# lora_mini_uno.net
KiCad netlist of a schematic drawn in EAGLE
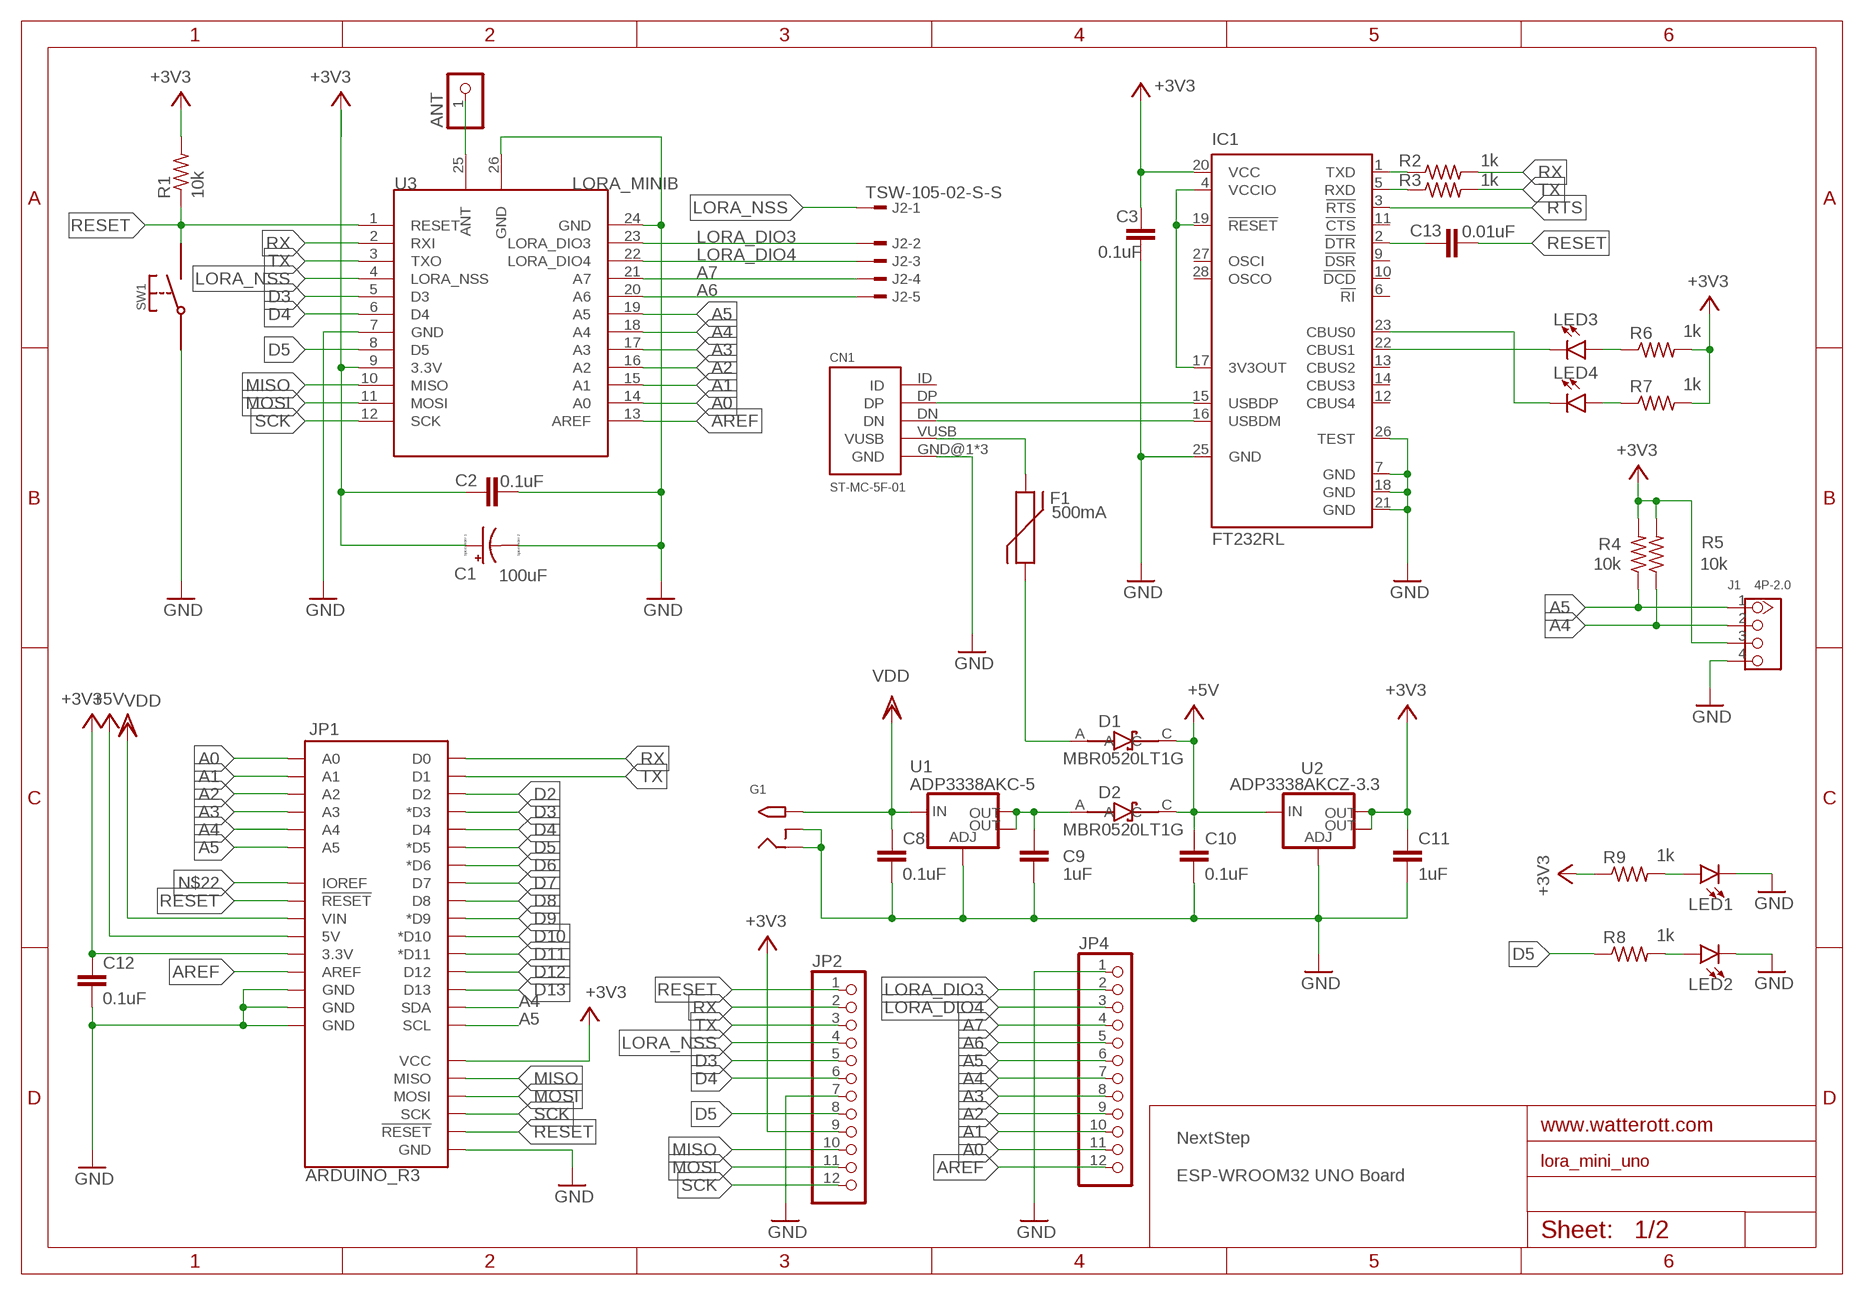
[diagram p0: schematic, sheet 1]
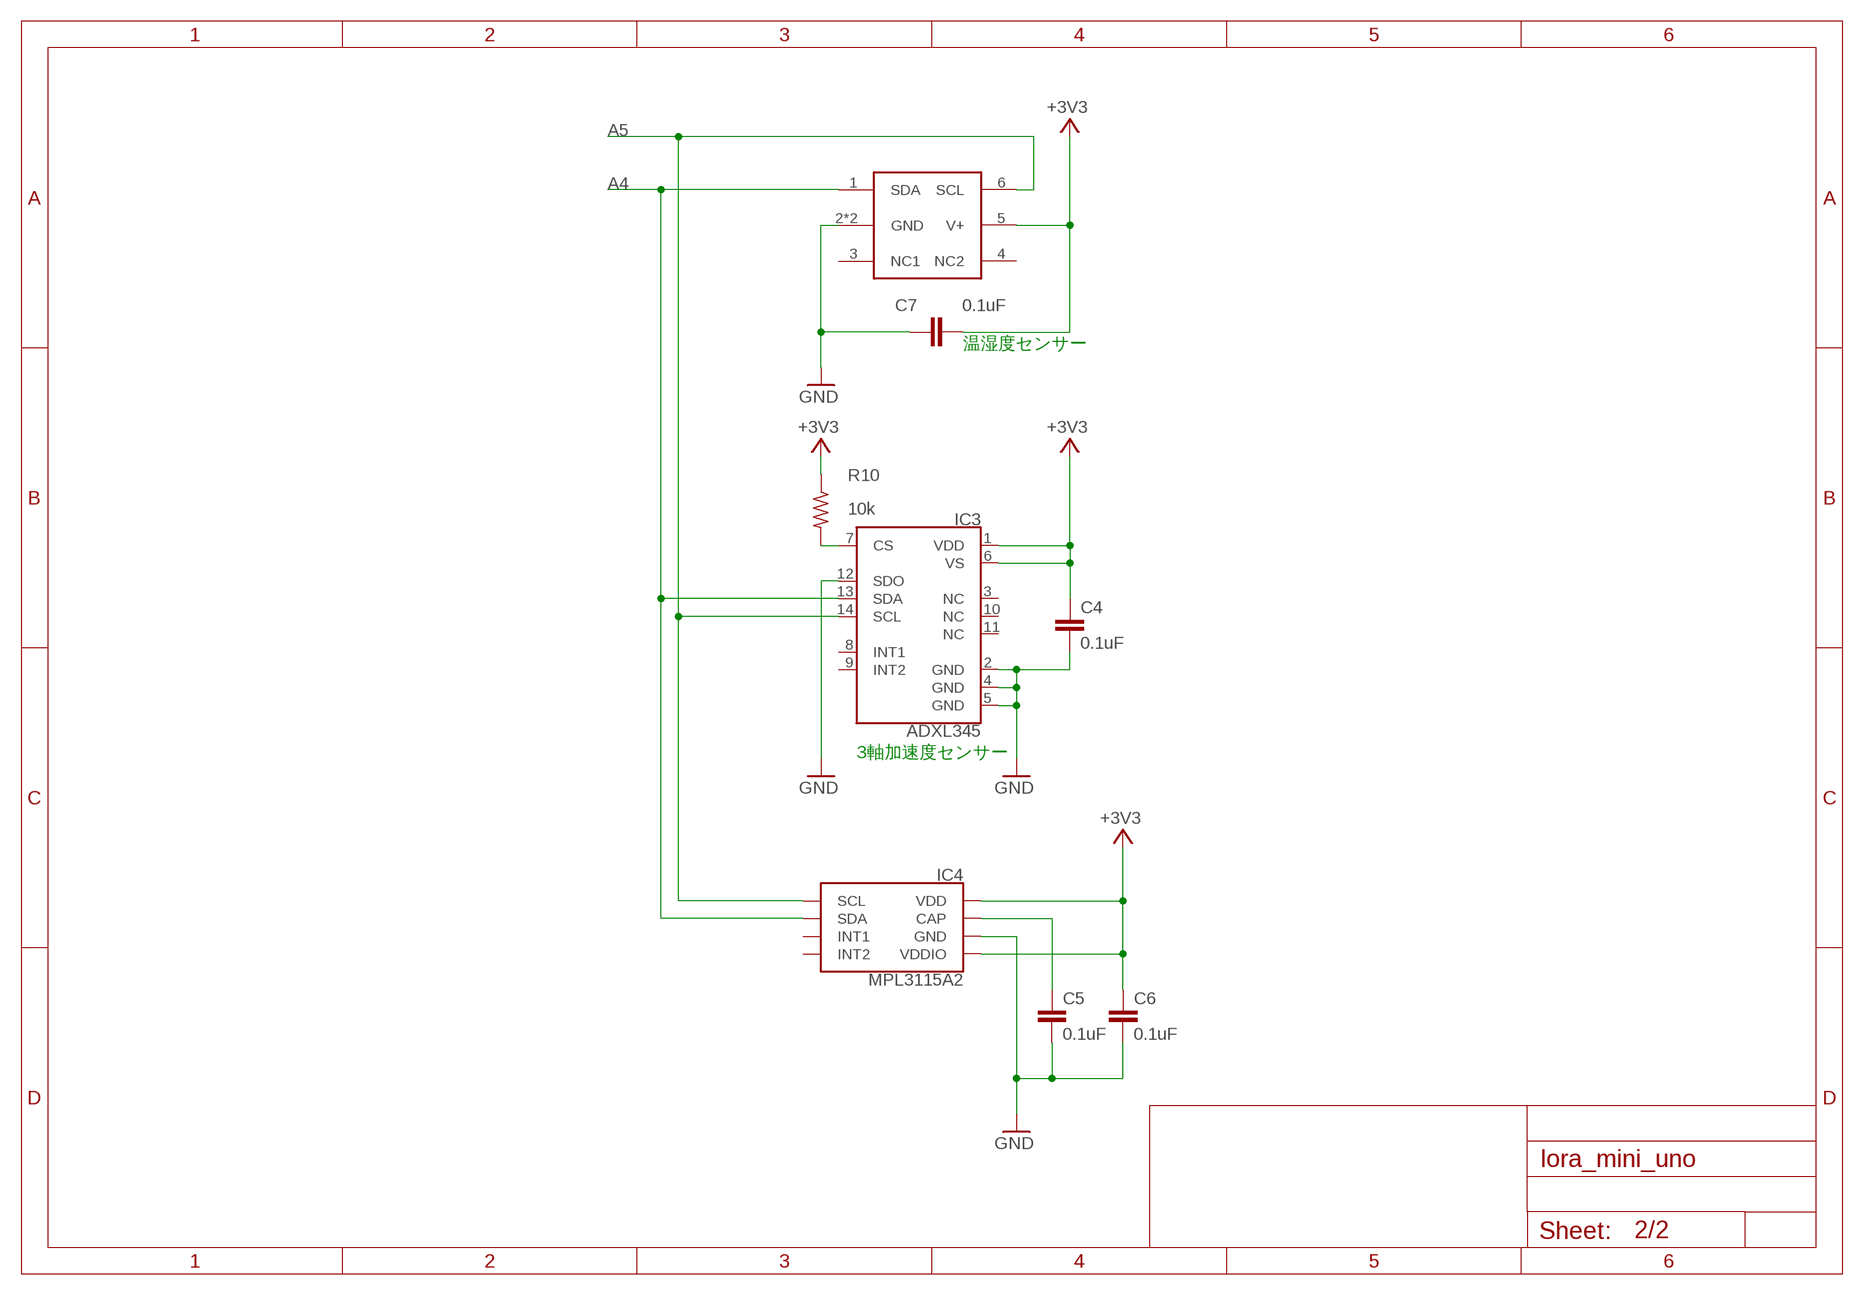
[diagram p1: schematic, sheet 2]

(export (version "E")
  (design (tool "Eeschema 10.0.6"))
  (components
    (comp (ref "ANT")
      (value "PINHD-1X1")
      (footprint "eagle-import:1X01")
      (libsource (lib "eagle-import") (part "PINHD-1X1"))
    )
    (comp (ref "C1")
      (value "100uF")
      (footprint "eagle-import:153CLV-0505")
      (libsource (lib "eagle-import") (part "CPOL-US153CLV-0505"))
    )
    (comp (ref "C2")
      (value "0.1uF")
      (footprint "eagle-import:C0603K")
      (libsource (lib "eagle-import") (part "C-EUC0603K"))
    )
    (comp (ref "C3")
      (value "0.1uF")
      (footprint "eagle-import:C0603K")
      (libsource (lib "eagle-import") (part "C-EUC0603K"))
    )
    (comp (ref "C8")
      (value "0.1uF")
      (footprint "eagle-import:C0603K")
      (libsource (lib "eagle-import") (part "C-EUC0603K"))
    )
    (comp (ref "C9")
      (value "1uF")
      (footprint "eagle-import:C0603K")
      (libsource (lib "eagle-import") (part "C-EUC0603K"))
    )
    (comp (ref "C10")
      (value "0.1uF")
      (footprint "eagle-import:C0603K")
      (libsource (lib "eagle-import") (part "C-EUC0603K"))
    )
    (comp (ref "C11")
      (value "1uF")
      (footprint "eagle-import:C0603K")
      (libsource (lib "eagle-import") (part "C-EUC0603K"))
    )
    (comp (ref "C12")
      (value "0.1uF")
      (footprint "eagle-import:C0603K")
      (libsource (lib "eagle-import") (part "C-EUC0603K"))
    )
    (comp (ref "C13")
      (value "0.01uF")
      (footprint "eagle-import:C0603K")
      (libsource (lib "eagle-import") (part "C-EUC0603K"))
    )
    (comp (ref "CN1")
      (value "ST-MC-5F-01")
      (footprint "eagle-import:ST-MC-5F-01")
      (libsource (lib "eagle-import") (part "ST-MC-5F-01"))
    )
    (comp (ref "D1")
      (value "MBR0520LT1G")
      (footprint "eagle-import:SOD3716X135N")
      (fields (field (name "MF") "ON Semiconductor"))
      (libsource (lib "eagle-import") (part "MBR0520LT1G"))
    )
    (comp (ref "D2")
      (value "MBR0520LT1G")
      (footprint "eagle-import:SOD3716X135N")
      (fields (field (name "MF") "ON Semiconductor"))
      (libsource (lib "eagle-import") (part "MBR0520LT1G"))
    )
    (comp (ref "F1")
      (value "500mA")
      (footprint "eagle-import:R1206")
      (libsource (lib "eagle-import") (part "FUSE1206"))
    )
    (comp (ref "G1")
      (value "2.1MMJACKTHM")
      (footprint "eagle-import:PJ-102A")
      (libsource (lib "eagle-import") (part "2.1MMJACKTHM"))
    )
    (comp (ref "IC1")
      (value "FT232RL")
      (footprint "eagle-import:SSOP28")
      (libsource (lib "eagle-import") (part "FT232RL"))
    )
    (comp (ref "J1")
      (value "4P-2.0")
      (footprint "eagle-import:HW4-2.0")
      (libsource (lib "eagle-import") (part "GROVE-CONNECTOR-DIP(4P-2.0)"))
    )
    (comp (ref "J2")
      (value "TSW-105-02-S-S")
      (footprint "eagle-import:TSW-105-02-S-S")
      (libsource (lib "eagle-import") (part "TSW-105-02-S-S"))
    )
    (comp (ref "JP1")
      (value "ARDUINO_R3")
      (footprint "eagle-import:ARDUINO_R3")
      (libsource (lib "eagle-import") (part "ARDUINO_R3"))
    )
    (comp (ref "JP2")
      (value "PINHD-1X12-CB")
      (footprint "eagle-import:1X12-CB")
      (libsource (lib "eagle-import") (part "PINHD-1X12-CB"))
    )
    (comp (ref "JP4")
      (value "PINHD-1X12-CB")
      (footprint "eagle-import:1X12-CB")
      (libsource (lib "eagle-import") (part "PINHD-1X12-CB"))
    )
    (comp (ref "LED1")
      (value "LED0603")
      (footprint "eagle-import:LED-0603")
      (libsource (lib "eagle-import") (part "LED0603"))
    )
    (comp (ref "LED2")
      (value "LED0603")
      (footprint "eagle-import:LED-0603")
      (libsource (lib "eagle-import") (part "LED0603"))
    )
    (comp (ref "LED3")
      (value "LED0603")
      (footprint "eagle-import:LED-0603")
      (libsource (lib "eagle-import") (part "LED0603"))
    )
    (comp (ref "LED4")
      (value "LED0603")
      (footprint "eagle-import:LED-0603")
      (libsource (lib "eagle-import") (part "LED0603"))
    )
    (comp (ref "R1")
      (value "10k")
      (footprint "eagle-import:R0603")
      (libsource (lib "eagle-import") (part "R-US_R0603"))
    )
    (comp (ref "R2")
      (value "1k")
      (footprint "eagle-import:R0603")
      (libsource (lib "eagle-import") (part "R-US_R0603"))
    )
    (comp (ref "R3")
      (value "1k")
      (footprint "eagle-import:R0603")
      (libsource (lib "eagle-import") (part "R-US_R0603"))
    )
    (comp (ref "R4")
      (value "10k")
      (footprint "eagle-import:R0603")
      (libsource (lib "eagle-import") (part "R-US_R0603"))
    )
    (comp (ref "R5")
      (value "10k")
      (footprint "eagle-import:R0603")
      (libsource (lib "eagle-import") (part "R-US_R0603"))
    )
    (comp (ref "R6")
      (value "1k")
      (footprint "eagle-import:R0603")
      (libsource (lib "eagle-import") (part "R-US_R0603"))
    )
    (comp (ref "R7")
      (value "1k")
      (footprint "eagle-import:R0603")
      (libsource (lib "eagle-import") (part "R-US_R0603"))
    )
    (comp (ref "R8")
      (value "1k")
      (footprint "eagle-import:R0603")
      (libsource (lib "eagle-import") (part "R-US_R0603"))
    )
    (comp (ref "R9")
      (value "1k")
      (footprint "eagle-import:R0603")
      (libsource (lib "eagle-import") (part "R-US_R0603"))
    )
    (comp (ref "SW1")
      (value "RESET")
      (footprint "eagle-import:SWITCH_3X6X5MM")
      (libsource (lib "eagle-import") (part "SWITCH"))
    )
    (comp (ref "U1")
      (value "ADP3338AKC-5")
      (footprint "eagle-import:SOT223")
      (libsource (lib "eagle-import") (part "V_REG_LM1117SOT223"))
    )
    (comp (ref "U2")
      (value "ADP3338AKCZ-3.3")
      (footprint "eagle-import:SOT223")
      (libsource (lib "eagle-import") (part "V_REG_LM1117SOT223"))
    )
    (comp (ref "U3")
      (value "LORA_MINIB")
      (footprint "eagle-import:LORA_MINI_PCB")
      (libsource (lib "eagle-import") (part "LORA_MINIB"))
    )
    (comp (ref "C4")
      (value "0.1uF")
      (footprint "eagle-import:C0603K")
      (libsource (lib "eagle-import") (part "C-EUC0603K"))
    )
    (comp (ref "C5")
      (value "0.1uF")
      (footprint "eagle-import:C0603K")
      (libsource (lib "eagle-import") (part "C-EUC0603K"))
    )
    (comp (ref "C6")
      (value "0.1uF")
      (footprint "eagle-import:C0603K")
      (libsource (lib "eagle-import") (part "C-EUC0603K"))
    )
    (comp (ref "C7")
      (value "0.1uF")
      (footprint "eagle-import:C0603K")
      (libsource (lib "eagle-import") (part "C-EUC0603K"))
    )
    (comp (ref "IC2")
      (value "SHT21")
      (footprint "eagle-import:SHT21")
      (libsource (lib "eagle-import") (part "SHT21"))
    )
    (comp (ref "IC3")
      (value "ADXL345")
      (footprint "eagle-import:LGA-14")
      (libsource (lib "eagle-import") (part "ADXL345"))
    )
    (comp (ref "IC4")
      (value "MPL3115A2")
      (footprint "eagle-import:LGA-8-5X3")
      (libsource (lib "eagle-import") (part "MPL3115A2"))
    )
    (comp (ref "R10")
      (value "10k")
      (footprint "eagle-import:R0603")
      (libsource (lib "eagle-import") (part "R-US_R0603"))
    )
  )
  (nets
    (net (code "1") (name "+3V3") (class "Default")
      (node (ref "C1") (pin "+") (pinfunction "+_+") (pintype "passive"))
      (node (ref "C11") (pin "1") (pinfunction "1_1") (pintype "passive"))
      (node (ref "C12") (pin "1") (pinfunction "1_1") (pintype "passive"))
      (node (ref "C2") (pin "1") (pinfunction "1_1") (pintype "passive"))
      (node (ref "C3") (pin "1") (pinfunction "1_1") (pintype "passive"))
      (node (ref "C4") (pin "1") (pinfunction "1_1") (pintype "passive"))
      (node (ref "C6") (pin "1") (pinfunction "1_1") (pintype "passive"))
      (node (ref "C7") (pin "2") (pinfunction "2_2") (pintype "passive"))
      (node (ref "IC1") (pin "20") (pinfunction "VCC_20") (pintype "power_in"))
      (node (ref "IC2") (pin "5") (pinfunction "V+_5") (pintype "bidirectional"))
      (node (ref "IC3") (pin "1") (pinfunction "VDD_1") (pintype "bidirectional"))
      (node (ref "IC3") (pin "6") (pinfunction "VS_6") (pintype "bidirectional"))
      (node (ref "IC4") (pin "1") (pinfunction "VDD_1") (pintype "power_in"))
      (node (ref "IC4") (pin "4") (pinfunction "VDDIO_4") (pintype "power_in"))
      (node (ref "J1") (pin "3") (pinfunction "3_3") (pintype "bidirectional"))
      (node (ref "JP1") (pin "3.3V") (pinfunction "3.3V_3.3V") (pintype "bidirectional"))
      (node (ref "JP1") (pin "VCC") (pinfunction "VCC_VCC") (pintype "bidirectional"))
      (node (ref "JP2") (pin "9") (pinfunction "9_9") (pintype "passive"))
      (node (ref "R1") (pin "2") (pinfunction "2_2") (pintype "passive"))
      (node (ref "R10") (pin "1") (pinfunction "1_1") (pintype "passive"))
      (node (ref "R4") (pin "2") (pinfunction "2_2") (pintype "passive"))
      (node (ref "R5") (pin "2") (pinfunction "2_2") (pintype "passive"))
      (node (ref "R6") (pin "2") (pinfunction "2_2") (pintype "passive"))
      (node (ref "R7") (pin "2") (pinfunction "2_2") (pintype "passive"))
      (node (ref "R9") (pin "1") (pinfunction "1_1") (pintype "passive"))
      (node (ref "U2") (pin "2") (pinfunction "OUT_2") (pintype "output"))
      (node (ref "U2") (pin "4") (pinfunction "OUT_4") (pintype "output"))
      (node (ref "U3") (pin "9") (pinfunction "3.3V_9") (pintype "bidirectional"))
    )
    (net (code "2") (name "+5V") (class "Default")
      (node (ref "C10") (pin "1") (pinfunction "1_1") (pintype "passive"))
      (node (ref "D1") (pin "C") (pinfunction "C_C") (pintype "passive"))
      (node (ref "D2") (pin "C") (pinfunction "C_C") (pintype "passive"))
      (node (ref "JP1") (pin "5V") (pinfunction "5V_5V") (pintype "bidirectional"))
      (node (ref "U2") (pin "3") (pinfunction "IN_3") (pintype "input"))
    )
    (net (code "3") (name "A0") (class "Default")
      (node (ref "JP1") (pin "A0") (pinfunction "A0_A0") (pintype "bidirectional"))
      (node (ref "JP4") (pin "11") (pinfunction "11_11") (pintype "passive"))
      (node (ref "U3") (pin "14") (pinfunction "A0_14") (pintype "bidirectional"))
    )
    (net (code "4") (name "A1") (class "Default")
      (node (ref "JP1") (pin "A1") (pinfunction "A1_A1") (pintype "bidirectional"))
      (node (ref "JP4") (pin "10") (pinfunction "10_10") (pintype "passive"))
      (node (ref "U3") (pin "15") (pinfunction "A1_15") (pintype "bidirectional"))
    )
    (net (code "5") (name "A2") (class "Default")
      (node (ref "JP1") (pin "A2") (pinfunction "A2_A2") (pintype "bidirectional"))
      (node (ref "JP4") (pin "9") (pinfunction "9_9") (pintype "passive"))
      (node (ref "U3") (pin "16") (pinfunction "A2_16") (pintype "bidirectional"))
    )
    (net (code "6") (name "A3") (class "Default")
      (node (ref "JP1") (pin "A3") (pinfunction "A3_A3") (pintype "bidirectional"))
      (node (ref "JP4") (pin "8") (pinfunction "8_8") (pintype "passive"))
      (node (ref "U3") (pin "17") (pinfunction "A3_17") (pintype "bidirectional"))
    )
    (net (code "7") (name "A4") (class "Default")
      (node (ref "IC2") (pin "1") (pinfunction "SDA_1") (pintype "bidirectional"))
      (node (ref "IC3") (pin "13") (pinfunction "SDA_13") (pintype "bidirectional"))
      (node (ref "IC4") (pin "7") (pinfunction "SDA_7") (pintype "bidirectional"))
      (node (ref "J1") (pin "2") (pinfunction "2_2") (pintype "bidirectional"))
      (node (ref "JP1") (pin "A4") (pinfunction "A4_A4") (pintype "bidirectional"))
      (node (ref "JP1") (pin "SDA") (pinfunction "SDA_SDA") (pintype "bidirectional"))
      (node (ref "JP4") (pin "7") (pinfunction "7_7") (pintype "passive"))
      (node (ref "R5") (pin "1") (pinfunction "1_1") (pintype "passive"))
      (node (ref "U3") (pin "18") (pinfunction "A4_18") (pintype "bidirectional"))
    )
    (net (code "8") (name "A5") (class "Default")
      (node (ref "IC2") (pin "6") (pinfunction "SCL_6") (pintype "bidirectional"))
      (node (ref "IC3") (pin "14") (pinfunction "SCL_14") (pintype "bidirectional"))
      (node (ref "IC4") (pin "8") (pinfunction "SCL_8") (pintype "bidirectional"))
      (node (ref "J1") (pin "1") (pinfunction "1_1") (pintype "bidirectional"))
      (node (ref "JP1") (pin "A5") (pinfunction "A5_A5") (pintype "bidirectional"))
      (node (ref "JP1") (pin "SCL") (pinfunction "SCL_SCL") (pintype "bidirectional"))
      (node (ref "JP4") (pin "6") (pinfunction "6_6") (pintype "passive"))
      (node (ref "R4") (pin "1") (pinfunction "1_1") (pintype "passive"))
      (node (ref "U3") (pin "19") (pinfunction "A5_19") (pintype "bidirectional"))
    )
    (net (code "9") (name "A6") (class "Default")
      (node (ref "J2") (pin "5") (pinfunction "1_5") (pintype "passive"))
      (node (ref "JP4") (pin "5") (pinfunction "5_5") (pintype "passive"))
      (node (ref "U3") (pin "20") (pinfunction "A6_20") (pintype "bidirectional"))
    )
    (net (code "10") (name "A7") (class "Default")
      (node (ref "J2") (pin "4") (pinfunction "1_4") (pintype "passive"))
      (node (ref "JP4") (pin "4") (pinfunction "4_4") (pintype "passive"))
      (node (ref "U3") (pin "21") (pinfunction "A7_21") (pintype "bidirectional"))
    )
    (net (code "11") (name "AREF") (class "Default")
      (node (ref "JP1") (pin "AREF") (pinfunction "AREF_AREF") (pintype "bidirectional"))
      (node (ref "JP4") (pin "12") (pinfunction "12_12") (pintype "passive"))
      (node (ref "U3") (pin "13") (pinfunction "AREF_13") (pintype "bidirectional"))
    )
    (net (code "12") (name "D2") (class "Default")
      (node (ref "JP1") (pin "D2") (pinfunction "D2_D2") (pintype "bidirectional"))
    )
    (net (code "13") (name "D3") (class "Default")
      (node (ref "JP1") (pin "D3") (pinfunction "*D3_D3") (pintype "bidirectional"))
      (node (ref "JP2") (pin "5") (pinfunction "5_5") (pintype "passive"))
      (node (ref "U3") (pin "5") (pinfunction "D3_5") (pintype "bidirectional"))
    )
    (net (code "14") (name "D4") (class "Default")
      (node (ref "JP1") (pin "D4") (pinfunction "D4_D4") (pintype "bidirectional"))
      (node (ref "JP2") (pin "6") (pinfunction "6_6") (pintype "passive"))
      (node (ref "U3") (pin "6") (pinfunction "D4_6") (pintype "bidirectional"))
    )
    (net (code "15") (name "D5") (class "Default")
      (node (ref "JP1") (pin "D5") (pinfunction "*D5_D5") (pintype "bidirectional"))
      (node (ref "JP2") (pin "8") (pinfunction "8_8") (pintype "passive"))
      (node (ref "R8") (pin "1") (pinfunction "1_1") (pintype "passive"))
      (node (ref "U3") (pin "8") (pinfunction "D5_8") (pintype "bidirectional"))
    )
    (net (code "16") (name "D6") (class "Default")
      (node (ref "JP1") (pin "D6") (pinfunction "*D6_D6") (pintype "bidirectional"))
    )
    (net (code "17") (name "D7") (class "Default")
      (node (ref "JP1") (pin "D7") (pinfunction "D7_D7") (pintype "bidirectional"))
    )
    (net (code "18") (name "D8") (class "Default")
      (node (ref "JP1") (pin "D8") (pinfunction "D8_D8") (pintype "bidirectional"))
    )
    (net (code "19") (name "D9") (class "Default")
      (node (ref "JP1") (pin "D9") (pinfunction "*D9_D9") (pintype "bidirectional"))
    )
    (net (code "20") (name "D10") (class "Default")
      (node (ref "JP1") (pin "D10") (pinfunction "*D10_D10") (pintype "bidirectional"))
    )
    (net (code "21") (name "D11") (class "Default")
      (node (ref "JP1") (pin "D11") (pinfunction "*D11_D11") (pintype "bidirectional"))
    )
    (net (code "22") (name "D12") (class "Default")
      (node (ref "JP1") (pin "D12") (pinfunction "D12_D12") (pintype "bidirectional"))
    )
    (net (code "23") (name "D13") (class "Default")
      (node (ref "JP1") (pin "D13") (pinfunction "D13_D13") (pintype "bidirectional"))
    )
    (net (code "24") (name "GND") (class "Default")
      (node (ref "C1") (pin "-") (pinfunction "-_-") (pintype "passive"))
      (node (ref "C10") (pin "2") (pinfunction "2_2") (pintype "passive"))
      (node (ref "C11") (pin "2") (pinfunction "2_2") (pintype "passive"))
      (node (ref "C12") (pin "2") (pinfunction "2_2") (pintype "passive"))
      (node (ref "C2") (pin "2") (pinfunction "2_2") (pintype "passive"))
      (node (ref "C3") (pin "2") (pinfunction "2_2") (pintype "passive"))
      (node (ref "C4") (pin "2") (pinfunction "2_2") (pintype "passive"))
      (node (ref "C5") (pin "2") (pinfunction "2_2") (pintype "passive"))
      (node (ref "C6") (pin "2") (pinfunction "2_2") (pintype "passive"))
      (node (ref "C7") (pin "1") (pinfunction "1_1") (pintype "passive"))
      (node (ref "C8") (pin "2") (pinfunction "2_2") (pintype "passive"))
      (node (ref "C9") (pin "2") (pinfunction "2_2") (pintype "passive"))
      (node (ref "CN1") (pin "GND@1") (pinfunction "GND_GND@1") (pintype "power_in"))
      (node (ref "CN1") (pin "GND@2") (pinfunction "GND_GND@2") (pintype "power_in"))
      (node (ref "CN1") (pin "GND@3") (pinfunction "GND_GND@3") (pintype "power_in"))
      (node (ref "G1") (pin "RING") (pinfunction "RING_RING") (pintype "bidirectional"))
      (node (ref "G1") (pin "RING_SW") (pinfunction "RING_SW_RING_SW") (pintype "bidirectional"))
      (node (ref "IC1") (pin "18") (pinfunction "GND_18") (pintype "power_in"))
      (node (ref "IC1") (pin "21") (pinfunction "GND_21") (pintype "power_in"))
      (node (ref "IC1") (pin "25") (pinfunction "GND_25") (pintype "power_in"))
      (node (ref "IC1") (pin "26") (pinfunction "TEST_26") (pintype "input"))
      (node (ref "IC1") (pin "7") (pinfunction "GND_7") (pintype "power_in"))
      (node (ref "IC2") (pin "2") (pinfunction "GND_2") (pintype "bidirectional"))
      (node (ref "IC2") (pin "P$1") (pinfunction "GND_P$1") (pintype "bidirectional"))
      (node (ref "IC3") (pin "12") (pinfunction "SDO_12") (pintype "bidirectional"))
      (node (ref "IC3") (pin "2") (pinfunction "GND_2") (pintype "bidirectional"))
      (node (ref "IC3") (pin "4") (pinfunction "GND_4") (pintype "bidirectional"))
      (node (ref "IC3") (pin "5") (pinfunction "GND_5") (pintype "bidirectional"))
      (node (ref "IC4") (pin "3") (pinfunction "GND_3") (pintype "power_in"))
      (node (ref "J1") (pin "4") (pinfunction "4_4") (pintype "bidirectional"))
      (node (ref "JP1") (pin "GND@1") (pinfunction "GND_GND@1") (pintype "bidirectional"))
      (node (ref "JP1") (pin "GND@2") (pinfunction "GND_GND@2") (pintype "bidirectional"))
      (node (ref "JP1") (pin "GND@3") (pinfunction "GND_GND@3") (pintype "bidirectional"))
      (node (ref "JP1") (pin "GND@4") (pinfunction "GND_GND@4") (pintype "bidirectional"))
      (node (ref "JP2") (pin "7") (pinfunction "7_7") (pintype "passive"))
      (node (ref "JP4") (pin "1") (pinfunction "1_1") (pintype "passive"))
      (node (ref "LED1") (pin "C") (pinfunction "C_C") (pintype "passive"))
      (node (ref "LED2") (pin "C") (pinfunction "C_C") (pintype "passive"))
      (node (ref "SW1") (pin "P$1") (pinfunction "P$1_P$1") (pintype "bidirectional"))
      (node (ref "U1") (pin "1") (pinfunction "ADJ_1") (pintype "input"))
      (node (ref "U2") (pin "1") (pinfunction "ADJ_1") (pintype "input"))
      (node (ref "U3") (pin "24") (pinfunction "GND_24") (pintype "bidirectional"))
      (node (ref "U3") (pin "26") (pinfunction "GND_26") (pintype "bidirectional"))
      (node (ref "U3") (pin "7") (pinfunction "GND_7") (pintype "bidirectional"))
    )
    (net (code "25") (name "LORA_DIO3") (class "Default")
      (node (ref "J2") (pin "2") (pinfunction "1_2") (pintype "passive"))
      (node (ref "JP4") (pin "2") (pinfunction "2_2") (pintype "passive"))
      (node (ref "U3") (pin "23") (pinfunction "LORA_DIO3_23") (pintype "bidirectional"))
    )
    (net (code "26") (name "LORA_DIO4") (class "Default")
      (node (ref "J2") (pin "3") (pinfunction "1_3") (pintype "passive"))
      (node (ref "JP4") (pin "3") (pinfunction "3_3") (pintype "passive"))
      (node (ref "U3") (pin "22") (pinfunction "LORA_DIO4_22") (pintype "bidirectional"))
    )
    (net (code "27") (name "LORA_NSS") (class "Default")
      (node (ref "J2") (pin "1") (pinfunction "1_1") (pintype "passive"))
      (node (ref "JP2") (pin "4") (pinfunction "4_4") (pintype "passive"))
      (node (ref "U3") (pin "4") (pinfunction "LORA_NSS_4") (pintype "bidirectional"))
    )
    (net (code "28") (name "MISO") (class "Default")
      (node (ref "JP1") (pin "MISO") (pinfunction "MISO_MISO") (pintype "bidirectional"))
      (node (ref "JP2") (pin "10") (pinfunction "10_10") (pintype "passive"))
      (node (ref "U3") (pin "10") (pinfunction "MISO_10") (pintype "bidirectional"))
    )
    (net (code "29") (name "MOSI") (class "Default")
      (node (ref "JP1") (pin "MOSI") (pinfunction "MOSI_MOSI") (pintype "bidirectional"))
      (node (ref "JP2") (pin "11") (pinfunction "11_11") (pintype "passive"))
      (node (ref "U3") (pin "11") (pinfunction "MOSI_11") (pintype "bidirectional"))
    )
    (net (code "30") (name "N$22") (class "Default")
      (node (ref "JP1") (pin "IOREF") (pinfunction "IOREF_IOREF") (pintype "bidirectional"))
    )
    (net (code "31") (name "Net-(C9-Pad1)") (class "Default")
      (node (ref "C9") (pin "1") (pinfunction "1_1") (pintype "passive"))
      (node (ref "D2") (pin "A") (pinfunction "A_A") (pintype "passive"))
      (node (ref "U1") (pin "2") (pinfunction "OUT_2") (pintype "output"))
      (node (ref "U1") (pin "4") (pinfunction "OUT_4") (pintype "output"))
    )
    (net (code "32") (name "Net-(CN1-PadVUSB)") (class "Default")
      (node (ref "CN1") (pin "VUSB") (pinfunction "VUSB_VUSB") (pintype "bidirectional"))
      (node (ref "F1") (pin "2") (pinfunction "2_2") (pintype "passive"))
    )
    (net (code "33") (name "Net-(D1-PadA)") (class "Default")
      (node (ref "D1") (pin "A") (pinfunction "A_A") (pintype "passive"))
      (node (ref "F1") (pin "1") (pinfunction "1_1") (pintype "passive"))
    )
    (net (code "34") (name "Net-(IC1-3V3OUT)") (class "Default")
      (node (ref "IC1") (pin "17") (pinfunction "3V3OUT_17") (pintype "output"))
      (node (ref "IC1") (pin "19") (pinfunction "~{RESET}_19") (pintype "input"))
      (node (ref "IC1") (pin "4") (pinfunction "VCCIO_4") (pintype "power_in"))
    )
    (net (code "35") (name "Net-(IC1-CBUS0)") (class "Default")
      (node (ref "IC1") (pin "23") (pinfunction "CBUS0_23") (pintype "bidirectional"))
      (node (ref "LED4") (pin "C") (pinfunction "C_C") (pintype "passive"))
    )
    (net (code "36") (name "Net-(IC1-CBUS1)") (class "Default")
      (node (ref "IC1") (pin "22") (pinfunction "CBUS1_22") (pintype "bidirectional"))
      (node (ref "LED3") (pin "C") (pinfunction "C_C") (pintype "passive"))
    )
    (net (code "37") (name "Net-(IC1-RXD)") (class "Default")
      (node (ref "IC1") (pin "5") (pinfunction "RXD_5") (pintype "input"))
      (node (ref "R3") (pin "1") (pinfunction "1_1") (pintype "passive"))
    )
    (net (code "38") (name "Net-(IC1-TXD)") (class "Default")
      (node (ref "IC1") (pin "1") (pinfunction "TXD_1") (pintype "output"))
      (node (ref "R2") (pin "1") (pinfunction "1_1") (pintype "passive"))
    )
    (net (code "39") (name "Net-(IC1-USBDM)") (class "Default")
      (node (ref "CN1") (pin "DN") (pinfunction "DN_DN") (pintype "bidirectional"))
      (node (ref "IC1") (pin "16") (pinfunction "USBDM_16") (pintype "bidirectional"))
    )
    (net (code "40") (name "Net-(IC1-USBDP)") (class "Default")
      (node (ref "CN1") (pin "DP") (pinfunction "DP_DP") (pintype "bidirectional"))
      (node (ref "IC1") (pin "15") (pinfunction "USBDP_15") (pintype "bidirectional"))
    )
    (net (code "41") (name "Net-(IC1-~{DTR})") (class "Default")
      (node (ref "C13") (pin "1") (pinfunction "1_1") (pintype "passive"))
      (node (ref "IC1") (pin "2") (pinfunction "~{DTR}_2") (pintype "output"))
    )
    (net (code "42") (name "Net-(IC3-CS)") (class "Default")
      (node (ref "IC3") (pin "7") (pinfunction "CS_7") (pintype "bidirectional"))
      (node (ref "R10") (pin "2") (pinfunction "2_2") (pintype "passive"))
    )
    (net (code "43") (name "Net-(IC4-CAP)") (class "Default")
      (node (ref "C5") (pin "1") (pinfunction "1_1") (pintype "passive"))
      (node (ref "IC4") (pin "2") (pinfunction "CAP_2") (pintype "power_in"))
    )
    (net (code "44") (name "Net-(LED1-PadA)") (class "Default")
      (node (ref "LED1") (pin "A") (pinfunction "A_A") (pintype "passive"))
      (node (ref "R9") (pin "2") (pinfunction "2_2") (pintype "passive"))
    )
    (net (code "45") (name "Net-(LED2-PadA)") (class "Default")
      (node (ref "LED2") (pin "A") (pinfunction "A_A") (pintype "passive"))
      (node (ref "R8") (pin "2") (pinfunction "2_2") (pintype "passive"))
    )
    (net (code "46") (name "Net-(LED3-PadA)") (class "Default")
      (node (ref "LED3") (pin "A") (pinfunction "A_A") (pintype "passive"))
      (node (ref "R6") (pin "1") (pinfunction "1_1") (pintype "passive"))
    )
    (net (code "47") (name "Net-(LED4-PadA)") (class "Default")
      (node (ref "LED4") (pin "A") (pinfunction "A_A") (pintype "passive"))
      (node (ref "R7") (pin "1") (pinfunction "1_1") (pintype "passive"))
    )
    (net (code "48") (name "Net-(U3-ANT)") (class "Default")
      (node (ref "ANT") (pin "1") (pinfunction "1_1") (pintype "passive"))
      (node (ref "U3") (pin "25") (pinfunction "ANT_25") (pintype "bidirectional"))
    )
    (net (code "49") (name "RESET") (class "Default")
      (node (ref "C13") (pin "2") (pinfunction "2_2") (pintype "passive"))
      (node (ref "JP1") (pin "RESET@1") (pinfunction "~{RESET}_RESET@1") (pintype "bidirectional"))
      (node (ref "JP1") (pin "RESET@2") (pinfunction "~{RESET}_RESET@2") (pintype "bidirectional"))
      (node (ref "JP2") (pin "1") (pinfunction "1_1") (pintype "passive"))
      (node (ref "R1") (pin "1") (pinfunction "1_1") (pintype "passive"))
      (node (ref "SW1") (pin "P$2") (pinfunction "P$2_P$2") (pintype "bidirectional"))
      (node (ref "U3") (pin "1") (pinfunction "RESET_1") (pintype "bidirectional"))
    )
    (net (code "50") (name "RTS") (class "Default")
      (node (ref "IC1") (pin "3") (pinfunction "~{RTS}_3") (pintype "output"))
    )
    (net (code "51") (name "RX") (class "Default")
      (node (ref "JP1") (pin "D0") (pinfunction "D0_D0") (pintype "bidirectional"))
      (node (ref "JP2") (pin "2") (pinfunction "2_2") (pintype "passive"))
      (node (ref "R2") (pin "2") (pinfunction "2_2") (pintype "passive"))
      (node (ref "U3") (pin "2") (pinfunction "RXI_2") (pintype "bidirectional"))
    )
    (net (code "52") (name "SCK") (class "Default")
      (node (ref "JP1") (pin "SCK") (pinfunction "SCK_SCK") (pintype "bidirectional"))
      (node (ref "JP2") (pin "12") (pinfunction "12_12") (pintype "passive"))
      (node (ref "U3") (pin "12") (pinfunction "SCK_12") (pintype "bidirectional"))
    )
    (net (code "53") (name "TX") (class "Default")
      (node (ref "JP1") (pin "D1") (pinfunction "D1_D1") (pintype "bidirectional"))
      (node (ref "JP2") (pin "3") (pinfunction "3_3") (pintype "passive"))
      (node (ref "R3") (pin "2") (pinfunction "2_2") (pintype "passive"))
      (node (ref "U3") (pin "3") (pinfunction "TXO_3") (pintype "bidirectional"))
    )
    (net (code "54") (name "VDD") (class "Default")
      (node (ref "C8") (pin "1") (pinfunction "1_1") (pintype "passive"))
      (node (ref "G1") (pin "TIP") (pinfunction "TIP_TIP") (pintype "bidirectional"))
      (node (ref "JP1") (pin "VIN") (pinfunction "VIN_VIN") (pintype "bidirectional"))
      (node (ref "U1") (pin "3") (pinfunction "IN_3") (pintype "input"))
    )
    (net (code "55") (name "unconnected-(CN1-PadID)") (class "Default")
      (node (ref "CN1") (pin "ID") (pinfunction "ID_ID") (pintype "bidirectional"))
    )
    (net (code "56") (name "unconnected-(IC1-CBUS2-Pad13)") (class "Default")
      (node (ref "IC1") (pin "13") (pinfunction "CBUS2_13") (pintype "bidirectional"))
    )
    (net (code "57") (name "unconnected-(IC1-CBUS3-Pad14)") (class "Default")
      (node (ref "IC1") (pin "14") (pinfunction "CBUS3_14") (pintype "bidirectional"))
    )
    (net (code "58") (name "unconnected-(IC1-CBUS4-Pad12)") (class "Default")
      (node (ref "IC1") (pin "12") (pinfunction "CBUS4_12") (pintype "bidirectional"))
    )
    (net (code "59") (name "unconnected-(IC1-OSCI-Pad27)") (class "Default")
      (node (ref "IC1") (pin "27") (pinfunction "OSCI_27") (pintype "input"))
    )
    (net (code "60") (name "unconnected-(IC1-OSCO-Pad28)") (class "Default")
      (node (ref "IC1") (pin "28") (pinfunction "OSCO_28") (pintype "output"))
    )
    (net (code "61") (name "unconnected-(IC1-~{CTS}-Pad11)") (class "Default")
      (node (ref "IC1") (pin "11") (pinfunction "~{CTS}_11") (pintype "input"))
    )
    (net (code "62") (name "unconnected-(IC1-~{DCD}-Pad10)") (class "Default")
      (node (ref "IC1") (pin "10") (pinfunction "~{DCD}_10") (pintype "input"))
    )
    (net (code "63") (name "unconnected-(IC1-~{DSR}-Pad9)") (class "Default")
      (node (ref "IC1") (pin "9") (pinfunction "~{DSR}_9") (pintype "input"))
    )
    (net (code "64") (name "unconnected-(IC1-~{RI}-Pad6)") (class "Default")
      (node (ref "IC1") (pin "6") (pinfunction "~{RI}_6") (pintype "input"))
    )
    (net (code "65") (name "unconnected-(IC2-NC1-Pad3)") (class "Default")
      (node (ref "IC2") (pin "3") (pinfunction "NC1_3") (pintype "bidirectional"))
    )
    (net (code "66") (name "unconnected-(IC2-NC2-Pad4)") (class "Default")
      (node (ref "IC2") (pin "4") (pinfunction "NC2_4") (pintype "bidirectional"))
    )
    (net (code "67") (name "unconnected-(IC3-INT1-Pad8)") (class "Default")
      (node (ref "IC3") (pin "8") (pinfunction "INT1_8") (pintype "bidirectional"))
    )
    (net (code "68") (name "unconnected-(IC3-INT2-Pad9)") (class "Default")
      (node (ref "IC3") (pin "9") (pinfunction "INT2_9") (pintype "bidirectional"))
    )
    (net (code "69") (name "unconnected-(IC3-NC-Pad3)") (class "Default")
      (node (ref "IC3") (pin "3") (pinfunction "NC_3") (pintype "bidirectional"))
    )
    (net (code "70") (name "unconnected-(IC3-NC-Pad10)") (class "Default")
      (node (ref "IC3") (pin "10") (pinfunction "NC_10") (pintype "bidirectional"))
    )
    (net (code "71") (name "unconnected-(IC3-NC-Pad11)") (class "Default")
      (node (ref "IC3") (pin "11") (pinfunction "NC_11") (pintype "bidirectional"))
    )
    (net (code "72") (name "unconnected-(IC4-INT1-Pad6)") (class "Default")
      (node (ref "IC4") (pin "6") (pinfunction "INT1_6") (pintype "output"))
    )
    (net (code "73") (name "unconnected-(IC4-INT2-Pad5)") (class "Default")
      (node (ref "IC4") (pin "5") (pinfunction "INT2_5") (pintype "output"))
    )
  )
)
